# dice.net
KiCad netlist of a schematic drawn in EAGLE
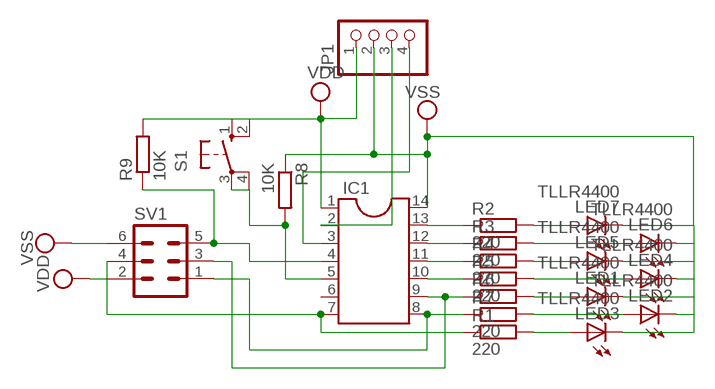
[diagram p0: schematic, sheet 1]

(export (version "E")
  (design (tool "Eeschema 10.0.6"))
  (components
    (comp (ref "IC1")
      (value "DIL14S")
      (footprint "eagle-import:SOCKET-14")
      (libsource (lib "eagle-import") (part "DIL14S"))
    )
    (comp (ref "JP1")
      (value "PINHD-1X4")
      (footprint "eagle-import:1X04")
      (libsource (lib "eagle-import") (part "PINHD-1X4"))
    )
    (comp (ref "LED1")
      (value "TLLR4400")
      (footprint "eagle-import:LED3MM")
      (fields (field (name "MF") "VISHAY SEMICONDUCTOR"))
      (libsource (lib "eagle-import") (part "TLLR4400"))
    )
    (comp (ref "LED2")
      (value "TLLR4400")
      (footprint "eagle-import:LED3MM")
      (fields (field (name "MF") "VISHAY SEMICONDUCTOR"))
      (libsource (lib "eagle-import") (part "TLLR4400"))
    )
    (comp (ref "LED3")
      (value "TLLR4400")
      (footprint "eagle-import:LED3MM")
      (fields (field (name "MF") "VISHAY SEMICONDUCTOR"))
      (libsource (lib "eagle-import") (part "TLLR4400"))
    )
    (comp (ref "LED4")
      (value "TLLR4400")
      (footprint "eagle-import:LED3MM")
      (fields (field (name "MF") "VISHAY SEMICONDUCTOR"))
      (libsource (lib "eagle-import") (part "TLLR4400"))
    )
    (comp (ref "LED5")
      (value "TLLR4400")
      (footprint "eagle-import:LED3MM")
      (fields (field (name "MF") "VISHAY SEMICONDUCTOR"))
      (libsource (lib "eagle-import") (part "TLLR4400"))
    )
    (comp (ref "LED6")
      (value "TLLR4400")
      (footprint "eagle-import:LED3MM")
      (fields (field (name "MF") "VISHAY SEMICONDUCTOR"))
      (libsource (lib "eagle-import") (part "TLLR4400"))
    )
    (comp (ref "LED7")
      (value "TLLR4400")
      (footprint "eagle-import:LED3MM")
      (fields (field (name "MF") "VISHAY SEMICONDUCTOR"))
      (libsource (lib "eagle-import") (part "TLLR4400"))
    )
    (comp (ref "R1")
      (value "220")
      (footprint "eagle-import:0204_7")
      (libsource (lib "eagle-import") (part "R0204/7"))
    )
    (comp (ref "R2")
      (value "220")
      (footprint "eagle-import:0204_7")
      (libsource (lib "eagle-import") (part "R0204/7"))
    )
    (comp (ref "R3")
      (value "220")
      (footprint "eagle-import:0204_7")
      (libsource (lib "eagle-import") (part "R0204/7"))
    )
    (comp (ref "R4")
      (value "220")
      (footprint "eagle-import:0204_7")
      (libsource (lib "eagle-import") (part "R0204/7"))
    )
    (comp (ref "R5")
      (value "220")
      (footprint "eagle-import:0204_7")
      (libsource (lib "eagle-import") (part "R0204/7"))
    )
    (comp (ref "R6")
      (value "R0204/7")
      (footprint "eagle-import:0204_7")
      (libsource (lib "eagle-import") (part "R0204/7"))
    )
    (comp (ref "R7")
      (value "220")
      (footprint "eagle-import:0204_7")
      (libsource (lib "eagle-import") (part "R0204/7"))
    )
    (comp (ref "R8")
      (value "10K")
      (footprint "eagle-import:0204_7")
      (libsource (lib "eagle-import") (part "R0204/7"))
    )
    (comp (ref "R9")
      (value "10K")
      (footprint "eagle-import:0204_7")
      (libsource (lib "eagle-import") (part "R0204/7"))
    )
    (comp (ref "S1")
      (value "10-XX")
      (footprint "eagle-import:B3F-10XX")
      (fields (field (name "MPN") "B3F-1000"))
      (libsource (lib "eagle-import") (part "10-XX"))
    )
    (comp (ref "SV1")
      (value "MA03-2")
      (footprint "eagle-import:MA03-2")
      (libsource (lib "eagle-import") (part "MA03-2"))
    )
  )
  (nets
    (net (code "1") (name "Net-(IC1-Pad2)") (class "Default")
      (node (ref "IC1") (pin "2") (pinfunction "2_2") (pintype "passive"))
      (node (ref "JP1") (pin "3") (pinfunction "3_3") (pintype "passive"))
    )
    (net (code "2") (name "Net-(IC1-Pad3)") (class "Default")
      (node (ref "IC1") (pin "3") (pinfunction "3_3") (pintype "passive"))
      (node (ref "JP1") (pin "4") (pinfunction "4_4") (pintype "passive"))
    )
    (net (code "3") (name "Net-(IC1-Pad4)") (class "Default")
      (node (ref "IC1") (pin "4") (pinfunction "4_4") (pintype "passive"))
      (node (ref "R9") (pin "1") (pinfunction "1_1") (pintype "passive"))
      (node (ref "SV1") (pin "5") (pinfunction "5_5") (pintype "passive"))
    )
    (net (code "4") (name "Net-(IC1-Pad7)") (class "Default")
      (node (ref "IC1") (pin "7") (pinfunction "7_7") (pintype "passive"))
      (node (ref "R1") (pin "1") (pinfunction "1_1") (pintype "passive"))
      (node (ref "SV1") (pin "4") (pinfunction "4_4") (pintype "passive"))
    )
    (net (code "5") (name "Net-(IC1-Pad8)") (class "Default")
      (node (ref "IC1") (pin "8") (pinfunction "8_8") (pintype "passive"))
      (node (ref "R7") (pin "1") (pinfunction "1_1") (pintype "passive"))
      (node (ref "SV1") (pin "1") (pinfunction "1_1") (pintype "passive"))
    )
    (net (code "6") (name "Net-(IC1-Pad9)") (class "Default")
      (node (ref "IC1") (pin "9") (pinfunction "9_9") (pintype "passive"))
      (node (ref "R6") (pin "1") (pinfunction "1_1") (pintype "passive"))
      (node (ref "SV1") (pin "3") (pinfunction "3_3") (pintype "passive"))
    )
    (net (code "7") (name "Net-(IC1-Pad10)") (class "Default")
      (node (ref "IC1") (pin "10") (pinfunction "10_10") (pintype "passive"))
      (node (ref "R5") (pin "1") (pinfunction "1_1") (pintype "passive"))
    )
    (net (code "8") (name "Net-(IC1-Pad11)") (class "Default")
      (node (ref "IC1") (pin "11") (pinfunction "11_11") (pintype "passive"))
      (node (ref "R4") (pin "1") (pinfunction "1_1") (pintype "passive"))
    )
    (net (code "9") (name "Net-(IC1-Pad12)") (class "Default")
      (node (ref "IC1") (pin "12") (pinfunction "12_12") (pintype "passive"))
      (node (ref "R3") (pin "1") (pinfunction "1_1") (pintype "passive"))
    )
    (net (code "10") (name "Net-(IC1-Pad13)") (class "Default")
      (node (ref "IC1") (pin "13") (pinfunction "13_13") (pintype "passive"))
      (node (ref "R2") (pin "1") (pinfunction "1_1") (pintype "passive"))
    )
    (net (code "11") (name "Net-(LED1-PadA)") (class "Default")
      (node (ref "LED1") (pin "A") (pinfunction "A_A") (pintype "passive"))
      (node (ref "R6") (pin "2") (pinfunction "2_2") (pintype "passive"))
    )
    (net (code "12") (name "Net-(LED2-PadA)") (class "Default")
      (node (ref "LED2") (pin "A") (pinfunction "A_A") (pintype "passive"))
      (node (ref "R7") (pin "2") (pinfunction "2_2") (pintype "passive"))
    )
    (net (code "13") (name "Net-(LED3-PadA)") (class "Default")
      (node (ref "LED3") (pin "A") (pinfunction "A_A") (pintype "passive"))
      (node (ref "R1") (pin "2") (pinfunction "2_2") (pintype "passive"))
    )
    (net (code "14") (name "Net-(LED4-PadA)") (class "Default")
      (node (ref "LED4") (pin "A") (pinfunction "A_A") (pintype "passive"))
      (node (ref "R5") (pin "2") (pinfunction "2_2") (pintype "passive"))
    )
    (net (code "15") (name "Net-(LED5-PadA)") (class "Default")
      (node (ref "LED5") (pin "A") (pinfunction "A_A") (pintype "passive"))
      (node (ref "R4") (pin "2") (pinfunction "2_2") (pintype "passive"))
    )
    (net (code "16") (name "Net-(LED6-PadA)") (class "Default")
      (node (ref "LED6") (pin "A") (pinfunction "A_A") (pintype "passive"))
      (node (ref "R3") (pin "2") (pinfunction "2_2") (pintype "passive"))
    )
    (net (code "17") (name "Net-(LED7-PadA)") (class "Default")
      (node (ref "LED7") (pin "A") (pinfunction "A_A") (pintype "passive"))
      (node (ref "R2") (pin "2") (pinfunction "2_2") (pintype "passive"))
    )
    (net (code "18") (name "Net-(S1-P)") (class "Default")
      (node (ref "IC1") (pin "5") (pinfunction "5_5") (pintype "passive"))
      (node (ref "R8") (pin "2") (pinfunction "2_2") (pintype "passive"))
      (node (ref "S1") (pin "3") (pinfunction "P_3") (pintype "passive"))
      (node (ref "S1") (pin "4") (pinfunction "P1_4") (pintype "passive"))
    )
    (net (code "19") (name "VDD") (class "Default")
      (node (ref "IC1") (pin "1") (pinfunction "1_1") (pintype "passive"))
      (node (ref "JP1") (pin "1") (pinfunction "1_1") (pintype "passive"))
      (node (ref "R9") (pin "2") (pinfunction "2_2") (pintype "passive"))
      (node (ref "S1") (pin "1") (pinfunction "S_1") (pintype "passive"))
      (node (ref "S1") (pin "2") (pinfunction "S1_2") (pintype "passive"))
      (node (ref "SV1") (pin "2") (pinfunction "2_2") (pintype "passive"))
    )
    (net (code "20") (name "VSS") (class "Default")
      (node (ref "IC1") (pin "14") (pinfunction "14_14") (pintype "passive"))
      (node (ref "JP1") (pin "2") (pinfunction "2_2") (pintype "passive"))
      (node (ref "LED1") (pin "K") (pinfunction "C_K") (pintype "passive"))
      (node (ref "LED2") (pin "K") (pinfunction "C_K") (pintype "passive"))
      (node (ref "LED3") (pin "K") (pinfunction "C_K") (pintype "passive"))
      (node (ref "LED4") (pin "K") (pinfunction "C_K") (pintype "passive"))
      (node (ref "LED5") (pin "K") (pinfunction "C_K") (pintype "passive"))
      (node (ref "LED6") (pin "K") (pinfunction "C_K") (pintype "passive"))
      (node (ref "LED7") (pin "K") (pinfunction "C_K") (pintype "passive"))
      (node (ref "R8") (pin "1") (pinfunction "1_1") (pintype "passive"))
      (node (ref "SV1") (pin "6") (pinfunction "6_6") (pintype "passive"))
    )
    (net (code "21") (name "unconnected-(IC1-Pad6)") (class "Default")
      (node (ref "IC1") (pin "6") (pinfunction "6_6") (pintype "passive"))
    )
  )
)
